# 01_Power.net
KiCad netlist of a schematic drawn in Altium Designer
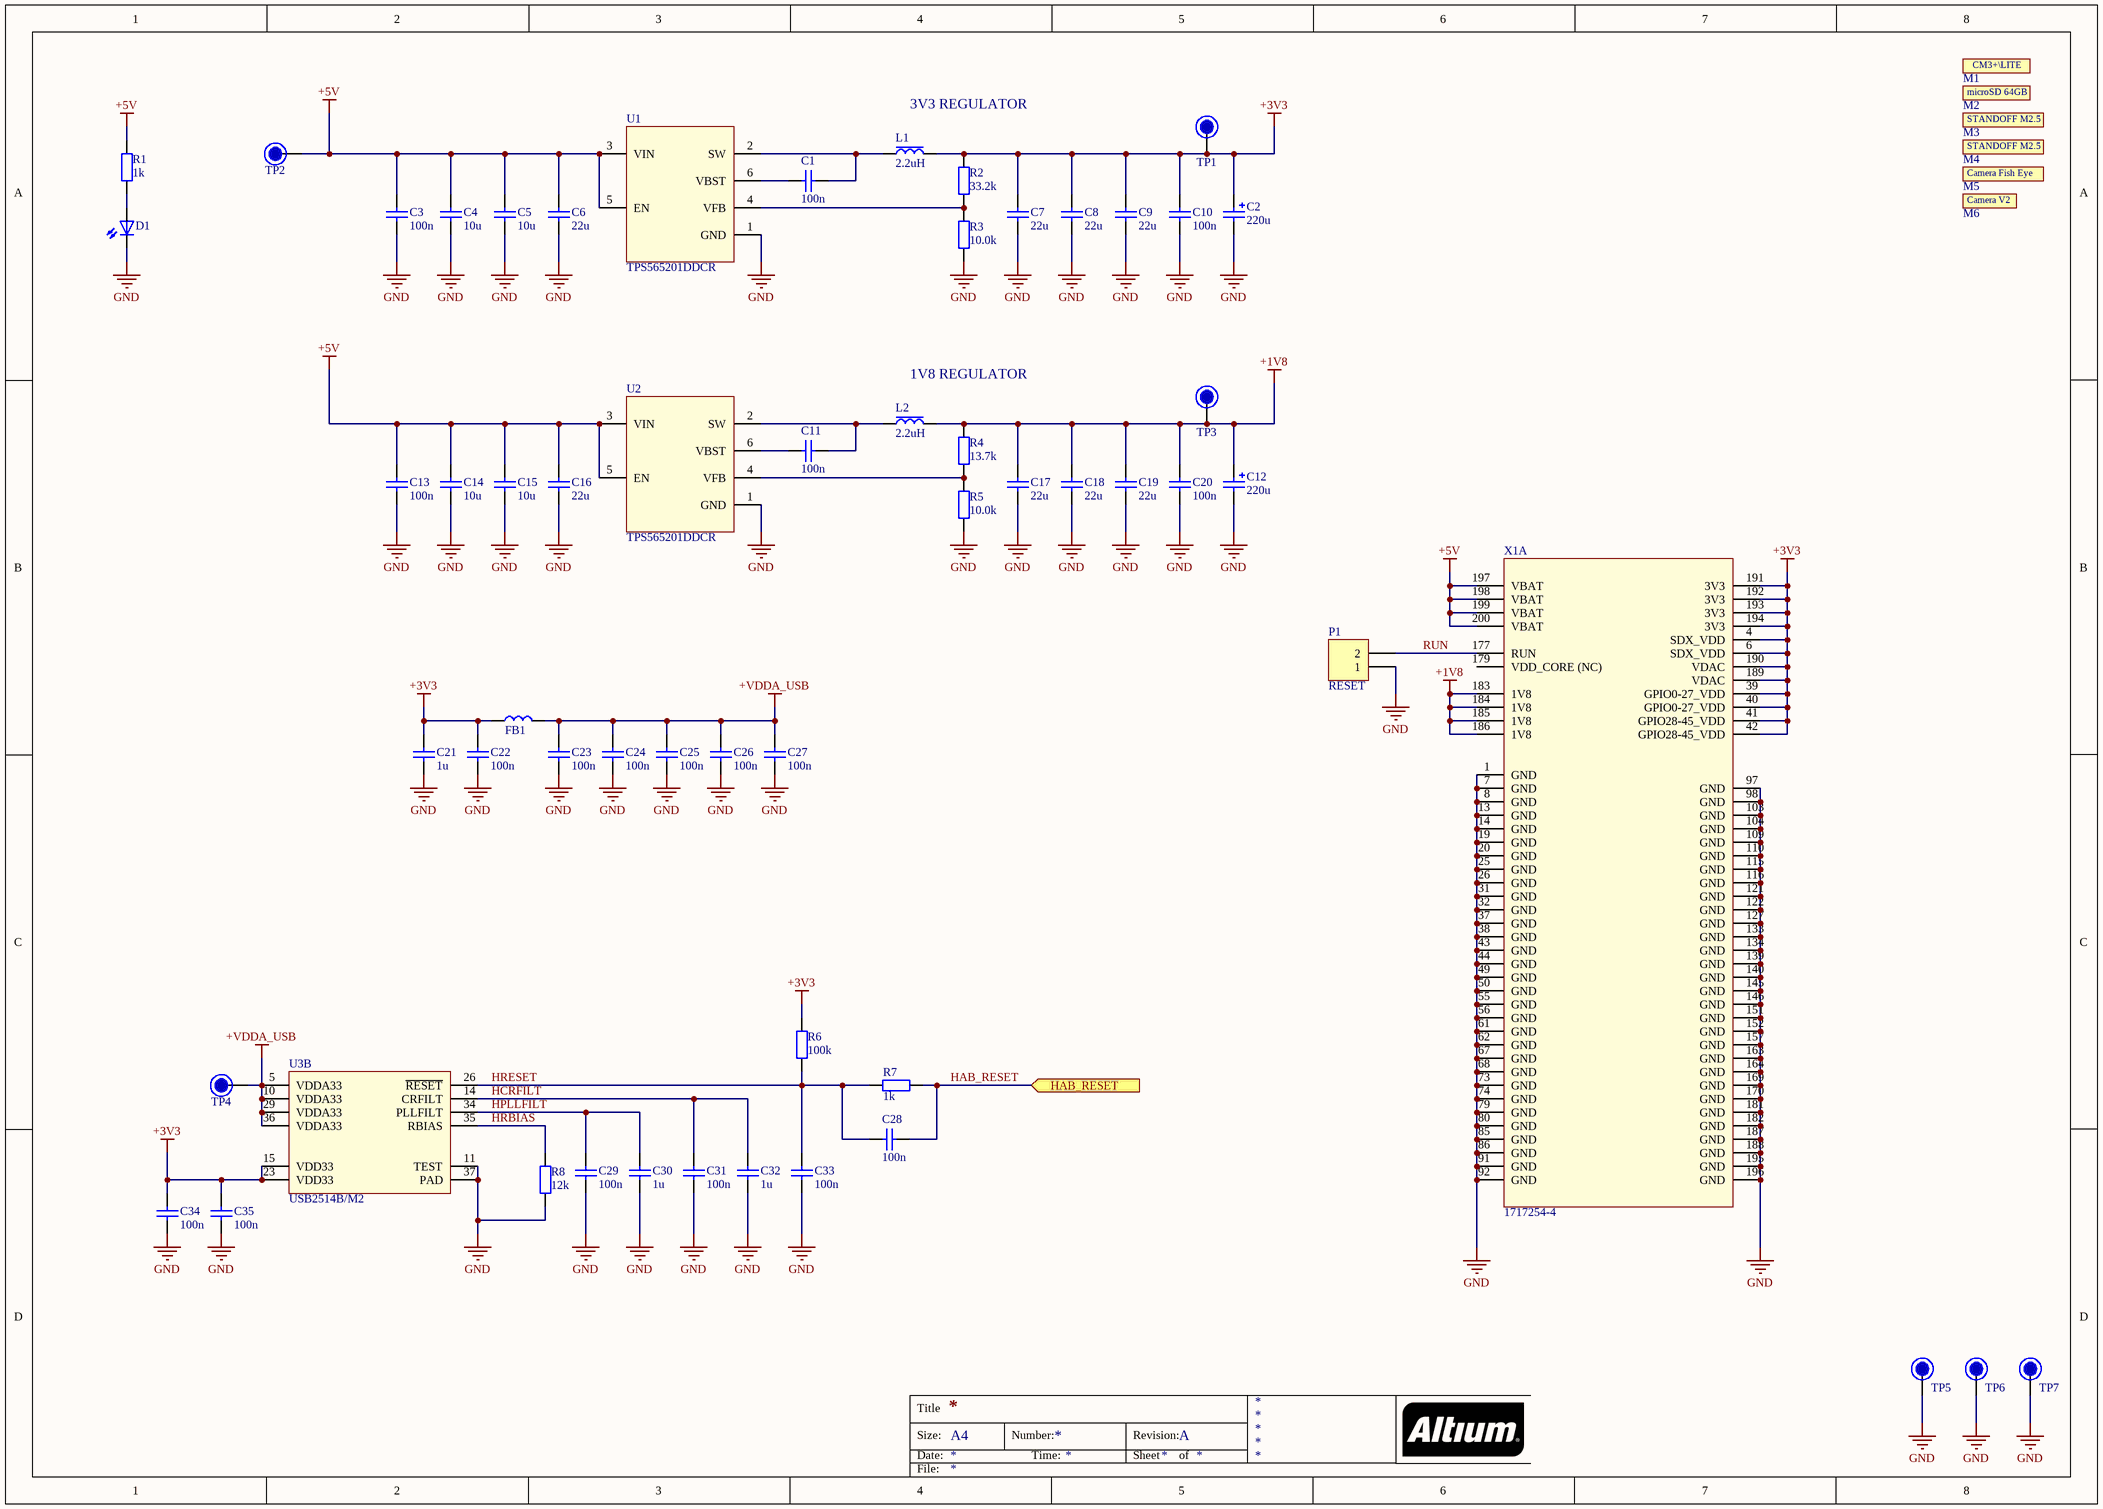
[diagram p0: 01_Power.SchDoc]

(export (version "E")
  (design (tool "Eeschema 10.0.6"))
  (components
    (comp (ref "C1")
      (value "100n")
      (footprint "C0603_IPC_HD")
      (description "CAP CER 0.1UF 16V X7R 0603")
      (fields
        (field (name "MANUFACTURER") "Samsung Electro-Mechanics")
        (field (name "MANUFACTURER PART NUMBER") "CL10B104KO8NNNC")
      )
      (libsource (lib "alfasat_lib") (part "CL10B104KO8NNNC"))
    )
    (comp (ref "C2")
      (value "220u")
      (footprint "TANT_CAP_7343")
      (description "Tantalum Capacitors 220uF 6.3V CASE-D_7343 RoHS")
      (fields (field (name "MANUFACTURER") "PANASONIC") (field (name "MANUFACTURER PART NUMBER") "6TPE220MI"))
      (libsource (lib "alfasat_parts_lib") (part "6TPE220MI"))
    )
    (comp (ref "C3")
      (value "100n")
      (footprint "C0603_IPC_HD")
      (description "CAP CER 0.1UF 16V X7R 0603")
      (fields
        (field (name "MANUFACTURER") "Samsung Electro-Mechanics")
        (field (name "MANUFACTURER PART NUMBER") "CL10B104KO8NNNC")
      )
      (libsource (lib "alfasat_lib") (part "CL10B104KO8NNNC"))
    )
    (comp (ref "C4")
      (value "10u")
      (footprint "C0805_IPC_HD")
      (description "CAP CER 10UF 16V X7R 0805")
      (fields
        (field (name "MANUFACTURER") "Samsung Electro-Mechanics")
        (field (name "MANUFACTURER PART NUMBER") "CL21B106KOQNNNG")
      )
      (libsource (lib "alfasat_lib") (part "CL21B106KOQNNNG"))
    )
    (comp (ref "C5")
      (value "10u")
      (footprint "C0805_IPC_HD")
      (description "CAP CER 10UF 16V X7R 0805")
      (fields
        (field (name "MANUFACTURER") "Samsung Electro-Mechanics")
        (field (name "MANUFACTURER PART NUMBER") "CL21B106KOQNNNG")
      )
      (libsource (lib "alfasat_lib") (part "CL21B106KOQNNNG"))
    )
    (comp (ref "C6")
      (value "22u")
      (footprint "C0805_IPC_HD")
      (description "CAP CER 22UF 16V X5R 0805")
      (fields
        (field (name "MANUFACTURER") "Samsung Electro-Mechanics")
        (field (name "MANUFACTURER PART NUMBER") "CL21A226MOCLRNC")
      )
      (libsource (lib "alfasat_lib") (part "CL21A226MOCLRNC"))
    )
    (comp (ref "C7")
      (value "22u")
      (footprint "C0805_IPC_HD")
      (description "CAP CER 22UF 16V X5R 0805")
      (fields
        (field (name "MANUFACTURER") "Samsung Electro-Mechanics")
        (field (name "MANUFACTURER PART NUMBER") "CL21A226MOCLRNC")
      )
      (libsource (lib "alfasat_lib") (part "CL21A226MOCLRNC"))
    )
    (comp (ref "C8")
      (value "22u")
      (footprint "C0805_IPC_HD")
      (description "CAP CER 22UF 16V X5R 0805")
      (fields
        (field (name "MANUFACTURER") "Samsung Electro-Mechanics")
        (field (name "MANUFACTURER PART NUMBER") "CL21A226MOCLRNC")
      )
      (libsource (lib "alfasat_lib") (part "CL21A226MOCLRNC"))
    )
    (comp (ref "C9")
      (value "22u")
      (footprint "C0805_IPC_HD")
      (description "CAP CER 22UF 16V X5R 0805")
      (fields
        (field (name "MANUFACTURER") "Samsung Electro-Mechanics")
        (field (name "MANUFACTURER PART NUMBER") "CL21A226MOCLRNC")
      )
      (libsource (lib "alfasat_lib") (part "CL21A226MOCLRNC"))
    )
    (comp (ref "C10")
      (value "100n")
      (footprint "C0603_IPC_HD")
      (description "CAP CER 0.1UF 16V X7R 0603")
      (fields
        (field (name "MANUFACTURER") "Samsung Electro-Mechanics")
        (field (name "MANUFACTURER PART NUMBER") "CL10B104KO8NNNC")
      )
      (libsource (lib "alfasat_lib") (part "CL10B104KO8NNNC"))
    )
    (comp (ref "C11")
      (value "100n")
      (footprint "C0603_IPC_HD")
      (description "CAP CER 0.1UF 16V X7R 0603")
      (fields
        (field (name "MANUFACTURER") "Samsung Electro-Mechanics")
        (field (name "MANUFACTURER PART NUMBER") "CL10B104KO8NNNC")
      )
      (libsource (lib "alfasat_lib") (part "CL10B104KO8NNNC"))
    )
    (comp (ref "C12")
      (value "220u")
      (footprint "TANT_CAP_7343")
      (description "Tantalum Capacitors 220uF 6.3V CASE-D_7343 RoHS")
      (fields (field (name "MANUFACTURER") "PANASONIC") (field (name "MANUFACTURER PART NUMBER") "6TPE220MI"))
      (libsource (lib "alfasat_parts_lib") (part "6TPE220MI"))
    )
    (comp (ref "C13")
      (value "100n")
      (footprint "C0603_IPC_HD")
      (description "CAP CER 0.1UF 16V X7R 0603")
      (fields
        (field (name "MANUFACTURER") "Samsung Electro-Mechanics")
        (field (name "MANUFACTURER PART NUMBER") "CL10B104KO8NNNC")
      )
      (libsource (lib "alfasat_lib") (part "CL10B104KO8NNNC"))
    )
    (comp (ref "C14")
      (value "10u")
      (footprint "C0805_IPC_HD")
      (description "CAP CER 10UF 16V X7R 0805")
      (fields
        (field (name "MANUFACTURER") "Samsung Electro-Mechanics")
        (field (name "MANUFACTURER PART NUMBER") "CL21B106KOQNNNG")
      )
      (libsource (lib "alfasat_lib") (part "CL21B106KOQNNNG"))
    )
    (comp (ref "C15")
      (value "10u")
      (footprint "C0805_IPC_HD")
      (description "CAP CER 10UF 16V X7R 0805")
      (fields
        (field (name "MANUFACTURER") "Samsung Electro-Mechanics")
        (field (name "MANUFACTURER PART NUMBER") "CL21B106KOQNNNG")
      )
      (libsource (lib "alfasat_lib") (part "CL21B106KOQNNNG"))
    )
    (comp (ref "C16")
      (value "22u")
      (footprint "C0805_IPC_HD")
      (description "CAP CER 22UF 16V X5R 0805")
      (fields
        (field (name "MANUFACTURER") "Samsung Electro-Mechanics")
        (field (name "MANUFACTURER PART NUMBER") "CL21A226MOCLRNC")
      )
      (libsource (lib "alfasat_lib") (part "CL21A226MOCLRNC"))
    )
    (comp (ref "C17")
      (value "22u")
      (footprint "C0805_IPC_HD")
      (description "CAP CER 22UF 16V X5R 0805")
      (fields
        (field (name "MANUFACTURER") "Samsung Electro-Mechanics")
        (field (name "MANUFACTURER PART NUMBER") "CL21A226MOCLRNC")
      )
      (libsource (lib "alfasat_lib") (part "CL21A226MOCLRNC"))
    )
    (comp (ref "C18")
      (value "22u")
      (footprint "C0805_IPC_HD")
      (description "CAP CER 22UF 16V X5R 0805")
      (fields
        (field (name "MANUFACTURER") "Samsung Electro-Mechanics")
        (field (name "MANUFACTURER PART NUMBER") "CL21A226MOCLRNC")
      )
      (libsource (lib "alfasat_lib") (part "CL21A226MOCLRNC"))
    )
    (comp (ref "C19")
      (value "22u")
      (footprint "C0805_IPC_HD")
      (description "CAP CER 22UF 16V X5R 0805")
      (fields
        (field (name "MANUFACTURER") "Samsung Electro-Mechanics")
        (field (name "MANUFACTURER PART NUMBER") "CL21A226MOCLRNC")
      )
      (libsource (lib "alfasat_lib") (part "CL21A226MOCLRNC"))
    )
    (comp (ref "C20")
      (value "100n")
      (footprint "C0603_IPC_HD")
      (description "CAP CER 0.1UF 16V X7R 0603")
      (fields
        (field (name "MANUFACTURER") "Samsung Electro-Mechanics")
        (field (name "MANUFACTURER PART NUMBER") "CL10B104KO8NNNC")
      )
      (libsource (lib "alfasat_lib") (part "CL10B104KO8NNNC"))
    )
    (comp (ref "C21")
      (value "1u")
      (footprint "C0603_IPC_HD")
      (description "CAP CER 1UF 16V X7R 0603")
      (fields
        (field (name "MANUFACTURER") "Samsung Electro-Mechanics")
        (field (name "MANUFACTURER PART NUMBER") "CL10B105MO8NNWC")
      )
      (libsource (lib "alfasat_lib") (part "CL10B105MO8NNWC"))
    )
    (comp (ref "C22")
      (value "100n")
      (footprint "C0603_IPC_HD")
      (description "CAP CER 0.1UF 16V X7R 0603")
      (fields
        (field (name "MANUFACTURER") "Samsung Electro-Mechanics")
        (field (name "MANUFACTURER PART NUMBER") "CL10B104KO8NNNC")
      )
      (libsource (lib "alfasat_lib") (part "CL10B104KO8NNNC"))
    )
    (comp (ref "C23")
      (value "100n")
      (footprint "C0603_IPC_HD")
      (description "CAP CER 0.1UF 16V X7R 0603")
      (fields
        (field (name "MANUFACTURER") "Samsung Electro-Mechanics")
        (field (name "MANUFACTURER PART NUMBER") "CL10B104KO8NNNC")
      )
      (libsource (lib "alfasat_lib") (part "CL10B104KO8NNNC"))
    )
    (comp (ref "C24")
      (value "100n")
      (footprint "C0603_IPC_HD")
      (description "CAP CER 0.1UF 16V X7R 0603")
      (fields
        (field (name "MANUFACTURER") "Samsung Electro-Mechanics")
        (field (name "MANUFACTURER PART NUMBER") "CL10B104KO8NNNC")
      )
      (libsource (lib "alfasat_lib") (part "CL10B104KO8NNNC"))
    )
    (comp (ref "C25")
      (value "100n")
      (footprint "C0603_IPC_HD")
      (description "CAP CER 0.1UF 16V X7R 0603")
      (fields
        (field (name "MANUFACTURER") "Samsung Electro-Mechanics")
        (field (name "MANUFACTURER PART NUMBER") "CL10B104KO8NNNC")
      )
      (libsource (lib "alfasat_lib") (part "CL10B104KO8NNNC"))
    )
    (comp (ref "C26")
      (value "100n")
      (footprint "C0603_IPC_HD")
      (description "CAP CER 0.1UF 16V X7R 0603")
      (fields
        (field (name "MANUFACTURER") "Samsung Electro-Mechanics")
        (field (name "MANUFACTURER PART NUMBER") "CL10B104KO8NNNC")
      )
      (libsource (lib "alfasat_lib") (part "CL10B104KO8NNNC"))
    )
    (comp (ref "C27")
      (value "100n")
      (footprint "C0603_IPC_HD")
      (description "CAP CER 0.1UF 16V X7R 0603")
      (fields
        (field (name "MANUFACTURER") "Samsung Electro-Mechanics")
        (field (name "MANUFACTURER PART NUMBER") "CL10B104KO8NNNC")
      )
      (libsource (lib "alfasat_lib") (part "CL10B104KO8NNNC"))
    )
    (comp (ref "C28")
      (value "100n")
      (footprint "C0603_IPC_HD")
      (description "CAP CER 0.1UF 16V X7R 0603")
      (fields
        (field (name "MANUFACTURER") "Samsung Electro-Mechanics")
        (field (name "MANUFACTURER PART NUMBER") "CL10B104KO8NNNC")
      )
      (libsource (lib "alfasat_parts_lib") (part "CL10B104KO8NNNC"))
    )
    (comp (ref "C29")
      (value "100n")
      (footprint "C0603_IPC_HD")
      (description "CAP CER 0.1UF 16V X7R 0603")
      (fields
        (field (name "MANUFACTURER") "Samsung Electro-Mechanics")
        (field (name "MANUFACTURER PART NUMBER") "CL10B104KO8NNNC")
      )
      (libsource (lib "alfasat_lib") (part "CL10B104KO8NNNC"))
    )
    (comp (ref "C30")
      (value "1u")
      (footprint "C0603_IPC_HD")
      (description "CAP CER 1UF 16V X7R 0603")
      (fields
        (field (name "MANUFACTURER") "Samsung Electro-Mechanics")
        (field (name "MANUFACTURER PART NUMBER") "CL10B105MO8NNWC")
      )
      (libsource (lib "alfasat_lib") (part "CL10B105MO8NNWC"))
    )
    (comp (ref "C31")
      (value "100n")
      (footprint "C0603_IPC_HD")
      (description "CAP CER 0.1UF 16V X7R 0603")
      (fields
        (field (name "MANUFACTURER") "Samsung Electro-Mechanics")
        (field (name "MANUFACTURER PART NUMBER") "CL10B104KO8NNNC")
      )
      (libsource (lib "alfasat_lib") (part "CL10B104KO8NNNC"))
    )
    (comp (ref "C32")
      (value "1u")
      (footprint "C0603_IPC_HD")
      (description "CAP CER 1UF 16V X7R 0603")
      (fields
        (field (name "MANUFACTURER") "Samsung Electro-Mechanics")
        (field (name "MANUFACTURER PART NUMBER") "CL10B105MO8NNWC")
      )
      (libsource (lib "alfasat_lib") (part "CL10B105MO8NNWC"))
    )
    (comp (ref "C33")
      (value "100n")
      (footprint "C0603_IPC_HD")
      (description "CAP CER 0.1UF 16V X7R 0603")
      (fields
        (field (name "MANUFACTURER") "Samsung Electro-Mechanics")
        (field (name "MANUFACTURER PART NUMBER") "CL10B104KO8NNNC")
      )
      (libsource (lib "alfasat_lib") (part "CL10B104KO8NNNC"))
    )
    (comp (ref "C34")
      (value "100n")
      (footprint "C0603_IPC_HD")
      (description "CAP CER 0.1UF 16V X7R 0603")
      (fields
        (field (name "MANUFACTURER") "Samsung Electro-Mechanics")
        (field (name "MANUFACTURER PART NUMBER") "CL10B104KO8NNNC")
      )
      (libsource (lib "alfasat_lib") (part "CL10B104KO8NNNC"))
    )
    (comp (ref "C35")
      (value "100n")
      (footprint "C0603_IPC_HD")
      (description "CAP CER 0.1UF 16V X7R 0603")
      (fields
        (field (name "MANUFACTURER") "Samsung Electro-Mechanics")
        (field (name "MANUFACTURER PART NUMBER") "CL10B104KO8NNNC")
      )
      (libsource (lib "alfasat_lib") (part "CL10B104KO8NNNC"))
    )
    (comp (ref "D1")
      (value "LTST-C190GKT")
      (footprint "LED_0603")
      (description "LED GREEN CLEAR CHIP SMD 0603")
      (fields (field (name "MANUFACTURER") "Lite-On Inc."))
      (libsource (lib "alfasat_lib") (part "LTST-C190GKT"))
    )
    (comp (ref "FB1")
      (value "MH1608-601Y")
      (footprint "L0603_IPC_MD")
      (description "FERRITE BEAD 600R@100MHz 0603 for Power Line, 1000mA")
      (fields (field (name "MANUFACTURER") "Bourns Inc."))
      (libsource (lib "alfasat_lib") (part "MH1608-601Y"))
    )
    (comp (ref "L1")
      (value "2.2uH")
      (footprint "ASPI-0520LR")
      (description "FIXED IND 2.2UH 5.5A 36 MOHM SMD")
      (fields
        (field (name "MANUFACTURER") "Abracon LLC")
        (field (name "MANUFACTURER PART NUMBER") "ASPI-0520LR-2R2M-T2")
      )
      (libsource (lib "alfasat_lib") (part "ASPI-0520LR-2R2M-T2"))
    )
    (comp (ref "L2")
      (value "2.2uH")
      (footprint "ASPI-0520LR")
      (description "FIXED IND 2.2UH 5.5A 36 MOHM SMD")
      (fields
        (field (name "MANUFACTURER") "Abracon LLC")
        (field (name "MANUFACTURER PART NUMBER") "ASPI-0520LR-2R2M-T2")
      )
      (libsource (lib "alfasat_lib") (part "ASPI-0520LR-2R2M-T2"))
    )
    (comp (ref "M1")
      (value "CM3+/LITE")
      (description "RASPBERRY PI COMPUTE 3+ LITE")
      (fields (field (name "MANUFACTURER") "Raspberry Pi"))
      (libsource (lib "alfasat_lib") (part "CM3+/LITE"))
    )
    (comp (ref "M2")
      (value "SDCG2/­64GB")
      (description "MemoryCard Class 10, 64GB")
      (fields (field (name "MANUFACTURER") "Kingston"))
      (libsource (lib "alfasat_lib") (part "SDCG2/64GB"))
    )
    (comp (ref "M3")
      (value "9774030151R")
      (footprint "9774030151R")
      (description "RND STANDOFF M2.5X0.45 STEEL 3MM")
      (fields (field (name "MANUFACTURER") "Würth Elektronik"))
      (libsource (lib "alfasat_parts_lib") (part "STANDOFF_M2.5X0.45_3MM"))
    )
    (comp (ref "M4")
      (value "9774030151R")
      (footprint "9774030151R")
      (description "RND STANDOFF M2.5X0.45 STEEL 3MM")
      (fields (field (name "MANUFACTURER") "Würth Elektronik"))
      (libsource (lib "alfasat_parts_lib") (part "STANDOFF_M2.5X0.45_3MM"))
    )
    (comp (ref "M5")
      (value "FishEye")
      (description "RASPBERRY PI CAMERA MODULE V2")
      (fields (field (name "MANUFACTURER") "China"))
      (libsource (lib "alfasat_lib") (part "Camera Fish Eye"))
    )
    (comp (ref "M6")
      (value "913-2664")
      (description "RASPBERRY PI CAMERA MODULE V2")
      (fields (field (name "MANUFACTURER") "Raspberry Pi"))
      (libsource (lib "alfasat_lib") (part "Camera V2"))
    )
    (comp (ref "P1")
      (value "RESET")
      (footprint "HDR1X2")
      (description "Header, 2-Pin")
      (fields (field (name "PUBLISHER") "Altium Limited"))
      (libsource (lib "Miscellaneous Connectors") (part "Header 2"))
    )
    (comp (ref "R1")
      (value "1k")
      (footprint "R0603_IPC_MD")
      (description "RES SMD 1K OHM 5% 1/10W 0603")
      (fields
        (field (name "MANUFACTURER") "Bourns Inc.")
        (field (name "MANUFACTURER PART NUMBER") "CR0603-JW-102ELF")
      )
      (libsource (lib "") (part "CR0603-JW-102ELF_1"))
    )
    (comp (ref "R2")
      (value "33.2k")
      (footprint "R0603_IPC_MD")
      (description "RES 33.2K OHM 1% 1/10W 0603")
      (fields
        (field (name "MANUFACTURER") "Stackpole Electronics Inc")
        (field (name "MANUFACTURER PART NUMBER") "RMCF0603FT33K2")
      )
      (libsource (lib "alfasat_lib") (part "RMCF0603FT33K2"))
    )
    (comp (ref "R3")
      (value "10.0k")
      (footprint "R0603_IPC_MD")
      (description "RES 10K OHM 1% 1/10W 0603")
      (fields
        (field (name "MANUFACTURER") "Stackpole Electronics Inc")
        (field (name "MANUFACTURER PART NUMBER") "RMCF0603FT10K0")
      )
      (libsource (lib "alfasat_lib") (part "RMCF0603FT10K0"))
    )
    (comp (ref "R4")
      (value "13.7k")
      (footprint "R0603_IPC_MD")
      (description "RES 13.7K OHM 1% 1/10W 0603")
      (fields
        (field (name "MANUFACTURER") "Stackpole Electronics Inc")
        (field (name "MANUFACTURER PART NUMBER") "RMCF0603FT13K7")
      )
      (libsource (lib "alfasat_lib") (part "RMCF0603FT13K7"))
    )
    (comp (ref "R5")
      (value "10.0k")
      (footprint "R0603_IPC_MD")
      (description "RES 10K OHM 1% 1/10W 0603")
      (fields
        (field (name "MANUFACTURER") "Stackpole Electronics Inc")
        (field (name "MANUFACTURER PART NUMBER") "RMCF0603FT10K0")
      )
      (libsource (lib "alfasat_lib") (part "RMCF0603FT10K0"))
    )
    (comp (ref "R6")
      (value "100k")
      (footprint "R0603_IPC_MD")
      (description "RES 100K OHM 1% 1/10W 0603")
      (fields
        (field (name "MANUFACTURER") "Bourns Inc.")
        (field (name "MANUFACTURER PART NUMBER") "RMCF0603FT100K")
      )
      (libsource (lib "alfasat_lib") (part "RMCF0603FT100K"))
    )
    (comp (ref "R7")
      (value "1k")
      (footprint "R0603_IPC_MD")
      (description "RES SMD 1K OHM 5% 1/10W 0603")
      (fields
        (field (name "MANUFACTURER") "Bourns Inc.")
        (field (name "MANUFACTURER PART NUMBER") "CR0603-JW-102ELF")
      )
      (libsource (lib "alfasat_lib") (part "CR0603-JW-102ELF"))
    )
    (comp (ref "R8")
      (value "12k")
      (footprint "R0603_IPC_MD")
      (description "RES SMD 12K OHM 1% 1/10W 0603")
      (fields
        (field (name "MANUFACTURER") "Bourns Inc.")
        (field (name "MANUFACTURER PART NUMBER") "CR0603-FX-1202ELF")
      )
      (libsource (lib "alfasat_lib") (part "CR0603-FX-1202ELF"))
    )
    (comp (ref "TP1")
      (value "3V3")
      (footprint "TestPoint_1M5")
      (description "Test Point")
      (libsource (lib "alfasat_lib") (part "TP"))
    )
    (comp (ref "TP2")
      (value "5V")
      (footprint "TestPoint_1M5")
      (description "Test Point")
      (libsource (lib "alfasat_lib") (part "TP"))
    )
    (comp (ref "TP3")
      (value "1V8")
      (footprint "TestPoint_1M5")
      (description "Test Point")
      (libsource (lib "alfasat_lib") (part "TP"))
    )
    (comp (ref "TP4")
      (value "VDDA_USB")
      (footprint "TestPoint_1M5")
      (description "Test Point")
      (libsource (lib "alfasat_lib") (part "TP"))
    )
    (comp (ref "TP5")
      (value "Test Point")
      (footprint "TestPoint_1M5_TH")
      (libsource (lib "alfasat_parts_lib") (part "TP"))
    )
    (comp (ref "TP6")
      (value "Test Point")
      (footprint "TestPoint_1M5_TH")
      (libsource (lib "alfasat_parts_lib") (part "TP"))
    )
    (comp (ref "TP7")
      (value "Test Point")
      (footprint "TestPoint_1M5_TH")
      (libsource (lib "alfasat_parts_lib") (part "TP"))
    )
    (comp (ref "U1")
      (value "TPS565201DDCR")
      (footprint "SOT23-6_(TI)")
      (description "Buck Switching Regulator IC Positive Adjustable 0.76V 1 Output 5A SOT-23-6 Thin, TSOT-23-6")
      (fields (field (name "MANUFACTURER") "TI"))
      (libsource (lib "alfasat_lib") (part "TPS565201DDCR"))
    )
    (comp (ref "U2")
      (value "TPS565201DDCR")
      (footprint "SOT23-6_(TI)")
      (description "Buck Switching Regulator IC Positive Adjustable 0.76V 1 Output 5A SOT-23-6 Thin, TSOT-23-6")
      (fields (field (name "MANUFACTURER") "TI"))
      (libsource (lib "alfasat_lib") (part "TPS565201DDCR"))
    )
    (comp (ref "U3")
      (value "USB2514B/M2")
      (footprint "QFN36")
      (description "IC HUB CTLR 4PORT USB 2.0 HS 36S")
      (fields (field (name "MANUFACTURER") "Microchip Technology"))
      (libsource (lib "alfasat_lib") (part "USB2514B/M2"))
    )
    (comp (ref "X1")
      (value "1717254-4")
      (footprint "1717254-1")
      (description "CONN SKT SODIMM 200POS R/A SMD")
      (fields (field (name "MANUFACTURER") "TE Connectivity AMP Connectors"))
      (libsource (lib "alfasat_lib") (part "Raspberry CM Connector"))
    )
  )
  (nets
    (net (code "1") (name "+1V8") (class "Default")
      (node (ref "C12") (pin "1") (pinfunction "1_1") (pintype "passive"))
      (node (ref "C17") (pin "1") (pinfunction "1_1") (pintype "passive"))
      (node (ref "C18") (pin "1") (pinfunction "1_1") (pintype "passive"))
      (node (ref "C19") (pin "1") (pinfunction "1_1") (pintype "passive"))
      (node (ref "C20") (pin "1") (pinfunction "1_1") (pintype "passive"))
      (node (ref "L2") (pin "2") (pinfunction "2_2") (pintype "passive"))
      (node (ref "R4") (pin "2") (pinfunction "2_2") (pintype "passive"))
      (node (ref "TP3") (pin "0") (pinfunction "0_0") (pintype "passive"))
      (node (ref "X1") (pin "183") (pinfunction "1V8_183") (pintype "passive"))
      (node (ref "X1") (pin "184") (pinfunction "1V8_184") (pintype "passive"))
      (node (ref "X1") (pin "185") (pinfunction "1V8_185") (pintype "passive"))
      (node (ref "X1") (pin "186") (pinfunction "1V8_186") (pintype "passive"))
    )
    (net (code "2") (name "+3V3") (class "Default")
      (node (ref "C10") (pin "1") (pinfunction "1_1") (pintype "passive"))
      (node (ref "C2") (pin "1") (pinfunction "1_1") (pintype "passive"))
      (node (ref "C21") (pin "2") (pinfunction "2_2") (pintype "passive"))
      (node (ref "C22") (pin "2") (pinfunction "2_2") (pintype "passive"))
      (node (ref "C34") (pin "2") (pinfunction "2_2") (pintype "passive"))
      (node (ref "C35") (pin "2") (pinfunction "2_2") (pintype "passive"))
      (node (ref "C7") (pin "1") (pinfunction "1_1") (pintype "passive"))
      (node (ref "C8") (pin "1") (pinfunction "1_1") (pintype "passive"))
      (node (ref "C9") (pin "1") (pinfunction "1_1") (pintype "passive"))
      (node (ref "FB1") (pin "1") (pinfunction "1_1") (pintype "passive"))
      (node (ref "L1") (pin "2") (pinfunction "2_2") (pintype "passive"))
      (node (ref "R2") (pin "2") (pinfunction "2_2") (pintype "passive"))
      (node (ref "R6") (pin "2") (pinfunction "2_2") (pintype "passive"))
      (node (ref "TP1") (pin "0") (pinfunction "0_0") (pintype "passive"))
      (node (ref "U3") (pin "15") (pinfunction "VDD33_15") (pintype "passive"))
      (node (ref "U3") (pin "23") (pinfunction "VDD33_23") (pintype "passive"))
      (node (ref "X1") (pin "189") (pinfunction "VDAC_189") (pintype "passive"))
      (node (ref "X1") (pin "190") (pinfunction "VDAC_190") (pintype "passive"))
      (node (ref "X1") (pin "191") (pinfunction "3V3_191") (pintype "passive"))
      (node (ref "X1") (pin "192") (pinfunction "3V3_192") (pintype "passive"))
      (node (ref "X1") (pin "193") (pinfunction "3V3_193") (pintype "passive"))
      (node (ref "X1") (pin "194") (pinfunction "3V3_194") (pintype "passive"))
      (node (ref "X1") (pin "39") (pinfunction "GPIO0-27_VDD_39") (pintype "passive"))
      (node (ref "X1") (pin "4") (pinfunction "SDX_VDD_4") (pintype "passive"))
      (node (ref "X1") (pin "40") (pinfunction "GPIO0-27_VDD_40") (pintype "passive"))
      (node (ref "X1") (pin "41") (pinfunction "GPIO28-45_VDD_41") (pintype "passive"))
      (node (ref "X1") (pin "42") (pinfunction "GPIO28-45_VDD_42") (pintype "passive"))
      (node (ref "X1") (pin "6") (pinfunction "SDX_VDD_6") (pintype "passive"))
    )
    (net (code "3") (name "+5V") (class "Default")
      (node (ref "C13") (pin "1") (pinfunction "1_1") (pintype "passive"))
      (node (ref "C14") (pin "2") (pinfunction "2_2") (pintype "passive"))
      (node (ref "C15") (pin "2") (pinfunction "2_2") (pintype "passive"))
      (node (ref "C16") (pin "1") (pinfunction "1_1") (pintype "passive"))
      (node (ref "C3") (pin "1") (pinfunction "1_1") (pintype "passive"))
      (node (ref "C4") (pin "2") (pinfunction "2_2") (pintype "passive"))
      (node (ref "C5") (pin "2") (pinfunction "2_2") (pintype "passive"))
      (node (ref "C6") (pin "1") (pinfunction "1_1") (pintype "passive"))
      (node (ref "R1") (pin "2") (pinfunction "2_2") (pintype "passive"))
      (node (ref "TP2") (pin "0") (pinfunction "0_0") (pintype "passive"))
      (node (ref "U1") (pin "3") (pinfunction "VIN_3") (pintype "passive"))
      (node (ref "U1") (pin "5") (pinfunction "EN_5") (pintype "passive"))
      (node (ref "U2") (pin "3") (pinfunction "VIN_3") (pintype "passive"))
      (node (ref "U2") (pin "5") (pinfunction "EN_5") (pintype "passive"))
      (node (ref "X1") (pin "197") (pinfunction "VBAT_197") (pintype "passive"))
      (node (ref "X1") (pin "198") (pinfunction "VBAT_198") (pintype "passive"))
      (node (ref "X1") (pin "199") (pinfunction "VBAT_199") (pintype "passive"))
      (node (ref "X1") (pin "200") (pinfunction "VBAT_200") (pintype "passive"))
    )
    (net (code "4") (name "+VDDA_USB") (class "Default")
      (node (ref "C23") (pin "2") (pinfunction "2_2") (pintype "passive"))
      (node (ref "C24") (pin "2") (pinfunction "2_2") (pintype "passive"))
      (node (ref "C25") (pin "2") (pinfunction "2_2") (pintype "passive"))
      (node (ref "C26") (pin "2") (pinfunction "2_2") (pintype "passive"))
      (node (ref "C27") (pin "2") (pinfunction "2_2") (pintype "passive"))
      (node (ref "FB1") (pin "2") (pinfunction "2_2") (pintype "passive"))
      (node (ref "TP4") (pin "0") (pinfunction "0_0") (pintype "passive"))
      (node (ref "U3") (pin "10") (pinfunction "VDDA33_10") (pintype "passive"))
      (node (ref "U3") (pin "29") (pinfunction "VDDA33_29") (pintype "passive"))
      (node (ref "U3") (pin "36") (pinfunction "VDDA33_36") (pintype "passive"))
      (node (ref "U3") (pin "5") (pinfunction "VDDA33_5") (pintype "passive"))
    )
    (net (code "5") (name "/HAB_RESET") (class "Default")
      (node (ref "C28") (pin "1") (pinfunction "1_1") (pintype "passive"))
      (node (ref "R7") (pin "1") (pinfunction "1_1") (pintype "passive"))
    )
    (net (code "6") (name "/HCRFILT") (class "Default")
      (node (ref "C31") (pin "2") (pinfunction "2_2") (pintype "passive"))
      (node (ref "C32") (pin "2") (pinfunction "2_2") (pintype "passive"))
      (node (ref "U3") (pin "14") (pinfunction "CRFILT_14") (pintype "passive"))
    )
    (net (code "7") (name "/HPLLFILT") (class "Default")
      (node (ref "C29") (pin "2") (pinfunction "2_2") (pintype "passive"))
      (node (ref "C30") (pin "2") (pinfunction "2_2") (pintype "passive"))
      (node (ref "U3") (pin "34") (pinfunction "PLLFILT_34") (pintype "passive"))
    )
    (net (code "8") (name "/HRBIAS") (class "Default")
      (node (ref "R8") (pin "2") (pinfunction "2_2") (pintype "passive"))
      (node (ref "U3") (pin "35") (pinfunction "RBIAS_35") (pintype "passive"))
    )
    (net (code "9") (name "/HRESET") (class "Default")
      (node (ref "C28") (pin "2") (pinfunction "2_2") (pintype "passive"))
      (node (ref "C33") (pin "1") (pinfunction "1_1") (pintype "passive"))
      (node (ref "R6") (pin "1") (pinfunction "1_1") (pintype "passive"))
      (node (ref "R7") (pin "2") (pinfunction "2_2") (pintype "passive"))
      (node (ref "U3") (pin "26") (pinfunction "~{RESET}_26") (pintype "passive"))
    )
    (net (code "10") (name "/RUN") (class "Default")
      (node (ref "P1") (pin "2") (pinfunction "2_2") (pintype "passive"))
      (node (ref "X1") (pin "177") (pinfunction "RUN_177") (pintype "passive"))
    )
    (net (code "11") (name "GND") (class "Default")
      (node (ref "C10") (pin "2") (pinfunction "2_2") (pintype "passive"))
      (node (ref "C12") (pin "2") (pinfunction "2_2") (pintype "passive"))
      (node (ref "C13") (pin "2") (pinfunction "2_2") (pintype "passive"))
      (node (ref "C14") (pin "1") (pinfunction "1_1") (pintype "passive"))
      (node (ref "C15") (pin "1") (pinfunction "1_1") (pintype "passive"))
      (node (ref "C16") (pin "2") (pinfunction "2_2") (pintype "passive"))
      (node (ref "C17") (pin "2") (pinfunction "2_2") (pintype "passive"))
      (node (ref "C18") (pin "2") (pinfunction "2_2") (pintype "passive"))
      (node (ref "C19") (pin "2") (pinfunction "2_2") (pintype "passive"))
      (node (ref "C2") (pin "2") (pinfunction "2_2") (pintype "passive"))
      (node (ref "C20") (pin "2") (pinfunction "2_2") (pintype "passive"))
      (node (ref "C21") (pin "1") (pinfunction "1_1") (pintype "passive"))
      (node (ref "C22") (pin "1") (pinfunction "1_1") (pintype "passive"))
      (node (ref "C23") (pin "1") (pinfunction "1_1") (pintype "passive"))
      (node (ref "C24") (pin "1") (pinfunction "1_1") (pintype "passive"))
      (node (ref "C25") (pin "1") (pinfunction "1_1") (pintype "passive"))
      (node (ref "C26") (pin "1") (pinfunction "1_1") (pintype "passive"))
      (node (ref "C27") (pin "1") (pinfunction "1_1") (pintype "passive"))
      (node (ref "C29") (pin "1") (pinfunction "1_1") (pintype "passive"))
      (node (ref "C3") (pin "2") (pinfunction "2_2") (pintype "passive"))
      (node (ref "C30") (pin "1") (pinfunction "1_1") (pintype "passive"))
      (node (ref "C31") (pin "1") (pinfunction "1_1") (pintype "passive"))
      (node (ref "C32") (pin "1") (pinfunction "1_1") (pintype "passive"))
      (node (ref "C33") (pin "2") (pinfunction "2_2") (pintype "passive"))
      (node (ref "C34") (pin "1") (pinfunction "1_1") (pintype "passive"))
      (node (ref "C35") (pin "1") (pinfunction "1_1") (pintype "passive"))
      (node (ref "C4") (pin "1") (pinfunction "1_1") (pintype "passive"))
      (node (ref "C5") (pin "1") (pinfunction "1_1") (pintype "passive"))
      (node (ref "C6") (pin "2") (pinfunction "2_2") (pintype "passive"))
      (node (ref "C7") (pin "2") (pinfunction "2_2") (pintype "passive"))
      (node (ref "C8") (pin "2") (pinfunction "2_2") (pintype "passive"))
      (node (ref "C9") (pin "2") (pinfunction "2_2") (pintype "passive"))
      (node (ref "D1") (pin "1") (pinfunction "C_1") (pintype "passive"))
      (node (ref "P1") (pin "1") (pinfunction "1_1") (pintype "passive"))
      (node (ref "R3") (pin "1") (pinfunction "1_1") (pintype "passive"))
      (node (ref "R5") (pin "1") (pinfunction "1_1") (pintype "passive"))
      (node (ref "R8") (pin "1") (pinfunction "1_1") (pintype "passive"))
      (node (ref "TP5") (pin "0") (pinfunction "0_0") (pintype "passive"))
      (node (ref "TP6") (pin "0") (pinfunction "0_0") (pintype "passive"))
      (node (ref "TP7") (pin "0") (pinfunction "0_0") (pintype "passive"))
      (node (ref "U1") (pin "1") (pinfunction "GND_1") (pintype "passive"))
      (node (ref "U2") (pin "1") (pinfunction "GND_1") (pintype "passive"))
      (node (ref "U3") (pin "11") (pinfunction "TEST_11") (pintype "passive"))
      (node (ref "U3") (pin "37") (pinfunction "PAD_37") (pintype "passive"))
      (node (ref "X1") (pin "1") (pinfunction "GND_1") (pintype "passive"))
      (node (ref "X1") (pin "103") (pinfunction "GND_103") (pintype "passive"))
      (node (ref "X1") (pin "104") (pinfunction "GND_104") (pintype "passive"))
      (node (ref "X1") (pin "109") (pinfunction "GND_109") (pintype "passive"))
      (node (ref "X1") (pin "110") (pinfunction "GND_110") (pintype "passive"))
      (node (ref "X1") (pin "115") (pinfunction "GND_115") (pintype "passive"))
      (node (ref "X1") (pin "116") (pinfunction "GND_116") (pintype "passive"))
      (node (ref "X1") (pin "121") (pinfunction "GND_121") (pintype "passive"))
      (node (ref "X1") (pin "122") (pinfunction "GND_122") (pintype "passive"))
      (node (ref "X1") (pin "127") (pinfunction "GND_127") (pintype "passive"))
      (node (ref "X1") (pin "13") (pinfunction "GND_13") (pintype "passive"))
      (node (ref "X1") (pin "133") (pinfunction "GND_133") (pintype "passive"))
      (node (ref "X1") (pin "134") (pinfunction "GND_134") (pintype "passive"))
      (node (ref "X1") (pin "139") (pinfunction "GND_139") (pintype "passive"))
      (node (ref "X1") (pin "14") (pinfunction "GND_14") (pintype "passive"))
      (node (ref "X1") (pin "140") (pinfunction "GND_140") (pintype "passive"))
      (node (ref "X1") (pin "145") (pinfunction "GND_145") (pintype "passive"))
      (node (ref "X1") (pin "146") (pinfunction "GND_146") (pintype "passive"))
      (node (ref "X1") (pin "151") (pinfunction "GND_151") (pintype "passive"))
      (node (ref "X1") (pin "152") (pinfunction "GND_152") (pintype "passive"))
      (node (ref "X1") (pin "157") (pinfunction "GND_157") (pintype "passive"))
      (node (ref "X1") (pin "163") (pinfunction "GND_163") (pintype "passive"))
      (node (ref "X1") (pin "164") (pinfunction "GND_164") (pintype "passive"))
      (node (ref "X1") (pin "169") (pinfunction "GND_169") (pintype "passive"))
      (node (ref "X1") (pin "170") (pinfunction "GND_170") (pintype "passive"))
      (node (ref "X1") (pin "181") (pinfunction "GND_181") (pintype "passive"))
      (node (ref "X1") (pin "182") (pinfunction "GND_182") (pintype "passive"))
      (node (ref "X1") (pin "187") (pinfunction "GND_187") (pintype "passive"))
      (node (ref "X1") (pin "188") (pinfunction "GND_188") (pintype "passive"))
      (node (ref "X1") (pin "19") (pinfunction "GND_19") (pintype "passive"))
      (node (ref "X1") (pin "195") (pinfunction "GND_195") (pintype "passive"))
      (node (ref "X1") (pin "196") (pinfunction "GND_196") (pintype "passive"))
      (node (ref "X1") (pin "20") (pinfunction "GND_20") (pintype "passive"))
      (node (ref "X1") (pin "25") (pinfunction "GND_25") (pintype "passive"))
      (node (ref "X1") (pin "26") (pinfunction "GND_26") (pintype "passive"))
      (node (ref "X1") (pin "31") (pinfunction "GND_31") (pintype "passive"))
      (node (ref "X1") (pin "32") (pinfunction "GND_32") (pintype "passive"))
      (node (ref "X1") (pin "37") (pinfunction "GND_37") (pintype "passive"))
      (node (ref "X1") (pin "38") (pinfunction "GND_38") (pintype "passive"))
      (node (ref "X1") (pin "43") (pinfunction "GND_43") (pintype "passive"))
      (node (ref "X1") (pin "44") (pinfunction "GND_44") (pintype "passive"))
      (node (ref "X1") (pin "49") (pinfunction "GND_49") (pintype "passive"))
      (node (ref "X1") (pin "50") (pinfunction "GND_50") (pintype "passive"))
      (node (ref "X1") (pin "55") (pinfunction "GND_55") (pintype "passive"))
      (node (ref "X1") (pin "56") (pinfunction "GND_56") (pintype "passive"))
      (node (ref "X1") (pin "61") (pinfunction "GND_61") (pintype "passive"))
      (node (ref "X1") (pin "62") (pinfunction "GND_62") (pintype "passive"))
      (node (ref "X1") (pin "67") (pinfunction "GND_67") (pintype "passive"))
      (node (ref "X1") (pin "68") (pinfunction "GND_68") (pintype "passive"))
      (node (ref "X1") (pin "7") (pinfunction "GND_7") (pintype "passive"))
      (node (ref "X1") (pin "73") (pinfunction "GND_73") (pintype "passive"))
      (node (ref "X1") (pin "74") (pinfunction "GND_74") (pintype "passive"))
      (node (ref "X1") (pin "79") (pinfunction "GND_79") (pintype "passive"))
      (node (ref "X1") (pin "8") (pinfunction "GND_8") (pintype "passive"))
      (node (ref "X1") (pin "80") (pinfunction "GND_80") (pintype "passive"))
      (node (ref "X1") (pin "85") (pinfunction "GND_85") (pintype "passive"))
      (node (ref "X1") (pin "86") (pinfunction "GND_86") (pintype "passive"))
      (node (ref "X1") (pin "91") (pinfunction "GND_91") (pintype "passive"))
      (node (ref "X1") (pin "92") (pinfunction "GND_92") (pintype "passive"))
      (node (ref "X1") (pin "97") (pinfunction "GND_97") (pintype "passive"))
      (node (ref "X1") (pin "98") (pinfunction "GND_98") (pintype "passive"))
    )
    (net (code "12") (name "Net-(D1-A)") (class "Default")
      (node (ref "D1") (pin "2") (pinfunction "A_2") (pintype "passive"))
      (node (ref "R1") (pin "1") (pinfunction "1_1") (pintype "passive"))
    )
    (net (code "13") (name "Net-(U1-SW)") (class "Default")
      (node (ref "C1") (pin "1") (pinfunction "1_1") (pintype "passive"))
      (node (ref "L1") (pin "1") (pinfunction "1_1") (pintype "passive"))
      (node (ref "U1") (pin "2") (pinfunction "SW_2") (pintype "passive"))
    )
    (net (code "14") (name "Net-(U1-VBST)") (class "Default")
      (node (ref "C1") (pin "2") (pinfunction "2_2") (pintype "passive"))
      (node (ref "U1") (pin "6") (pinfunction "VBST_6") (pintype "passive"))
    )
    (net (code "15") (name "Net-(U1-VFB)") (class "Default")
      (node (ref "R2") (pin "1") (pinfunction "1_1") (pintype "passive"))
      (node (ref "R3") (pin "2") (pinfunction "2_2") (pintype "passive"))
      (node (ref "U1") (pin "4") (pinfunction "VFB_4") (pintype "passive"))
    )
    (net (code "16") (name "Net-(U2-SW)") (class "Default")
      (node (ref "C11") (pin "1") (pinfunction "1_1") (pintype "passive"))
      (node (ref "L2") (pin "1") (pinfunction "1_1") (pintype "passive"))
      (node (ref "U2") (pin "2") (pinfunction "SW_2") (pintype "passive"))
    )
    (net (code "17") (name "Net-(U2-VBST)") (class "Default")
      (node (ref "C11") (pin "2") (pinfunction "2_2") (pintype "passive"))
      (node (ref "U2") (pin "6") (pinfunction "VBST_6") (pintype "passive"))
    )
    (net (code "18") (name "Net-(U2-VFB)") (class "Default")
      (node (ref "R4") (pin "1") (pinfunction "1_1") (pintype "passive"))
      (node (ref "R5") (pin "2") (pinfunction "2_2") (pintype "passive"))
      (node (ref "U2") (pin "4") (pinfunction "VFB_4") (pintype "passive"))
    )
    (net (code "19") (name "unconnected-(X1A-VDD_CORE_(NC)-Pad179)") (class "Default")
      (node (ref "X1") (pin "179") (pinfunction "VDD_CORE_(NC)_179") (pintype "passive"))
    )
  )
)
